# DC-DC-Converters.net
KiCad netlist of a schematic drawn in Altium Designer
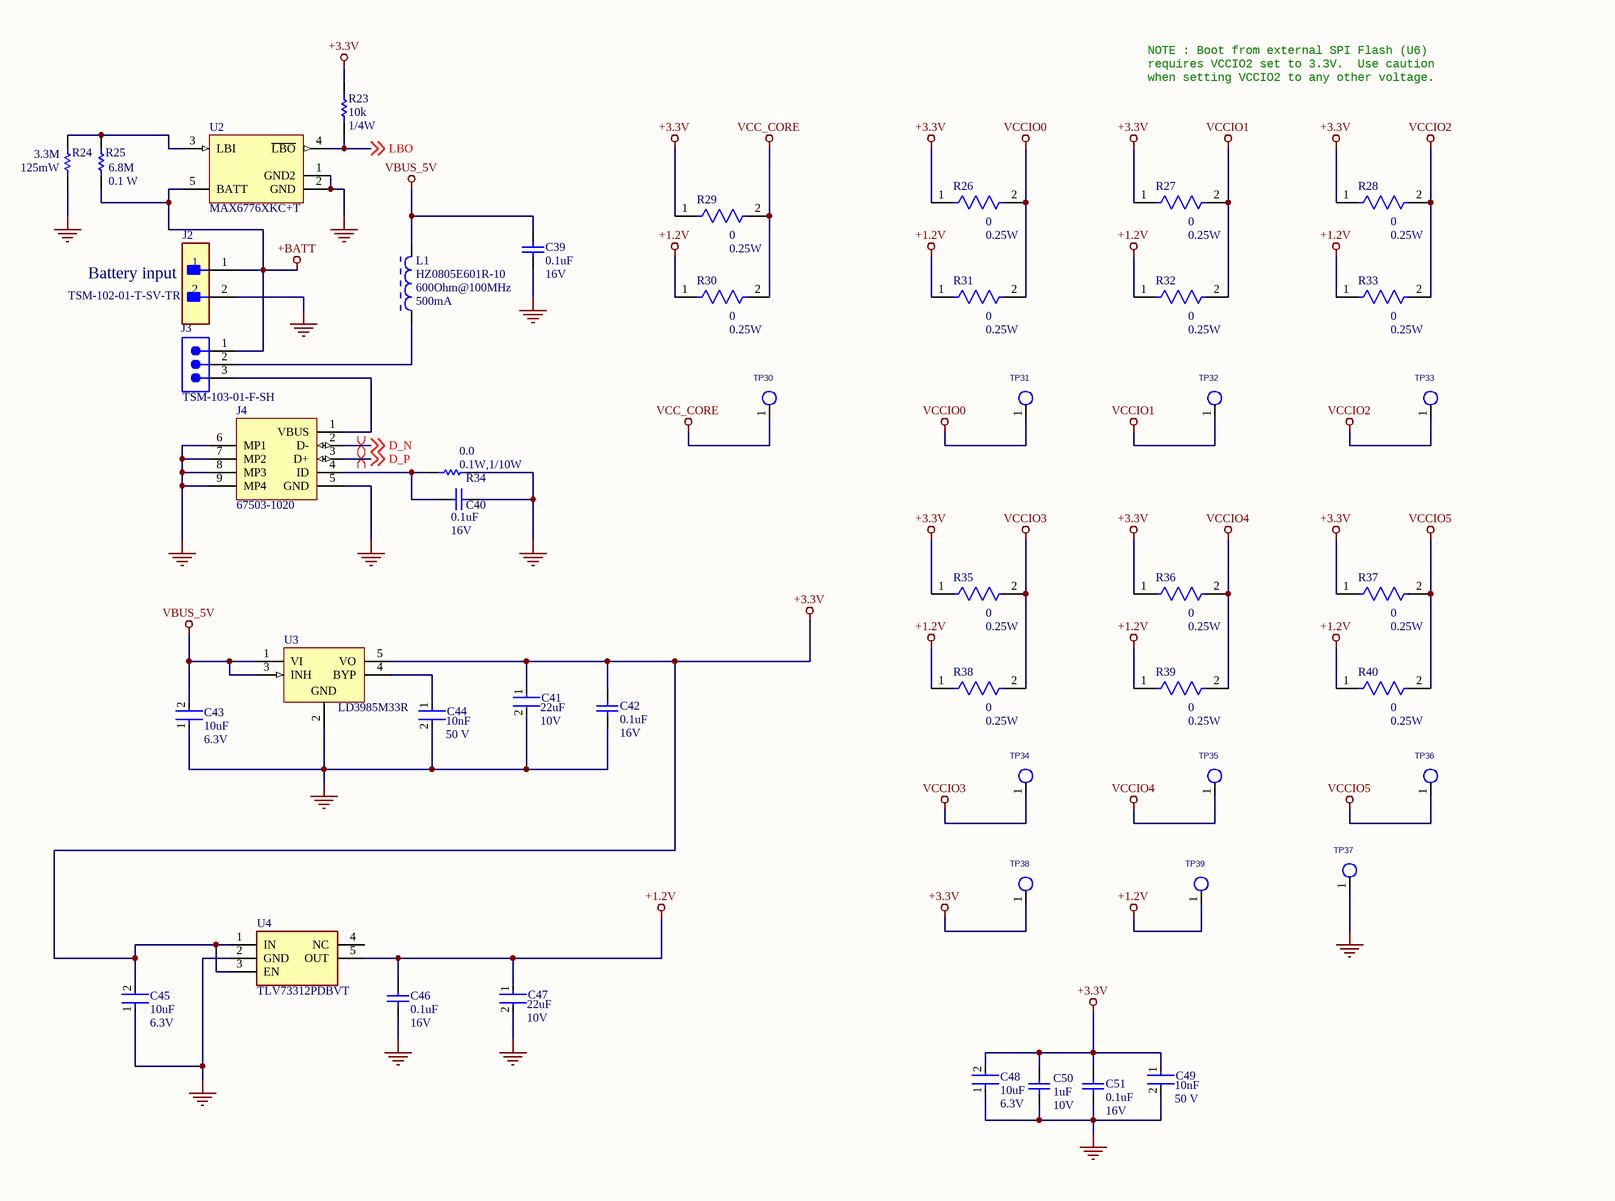
[diagram p0: DC-DC-Converters.SchDoc]

(export (version "E")
  (design (tool "Eeschema 10.0.6"))
  (components
    (comp (ref "C39")
      (value "0.1uF")
      (footprint "CAPC1608X87X35ML15T15")
      (description "Ceramic Capacitor 0.1uF 16V +-10% X7R0603")
      (fields
        (field (name "PART NUMBER") "C0603C104M4RACTU")
        (field (name "MANUFACTURER") "Kemet")
        (field (name "VOLTAGE") "16V")
      )
      (libsource (lib "Altium Content Vault") (part "CAP"))
    )
    (comp (ref "C40")
      (value "0.1uF")
      (footprint "CAPC1608X87X35ML15T15")
      (description "Ceramic Capacitor 0.1uF 16V +-10% X7R0603")
      (fields
        (field (name "PART NUMBER") "C0603C104M4RACTU")
        (field (name "MANUFACTURER") "Kemet")
        (field (name "VOLTAGE") "16V")
      )
      (libsource (lib "Altium Content Vault") (part "CAP"))
    )
    (comp (ref "C41")
      (value "22uF")
      (footprint "FP-GRM188-0_2-IPC_C")
      (description "Chip Multilayer Ceramic Capacitors for General Purpose, 0603, 22uF, X5R, 15%, 20%, 10V")
      (fields
        (field (name "TOLERANCE") "20%")
        (field (name "VOLTAGE") "10V")
        (field (name "PART NUMBER") "GRM188R61A226ME15D")
      )
      (libsource (lib "Altium Content Vault") (part "11868f565c42a9108669ba33697ecf6"))
    )
    (comp (ref "C42")
      (value "0.1uF")
      (footprint "CAPC1608X87X35ML15T15")
      (description "Ceramic Capacitor 0.1uF 16V +-10% X7R0603")
      (fields
        (field (name "PART NUMBER") "C0603C104M4RACTU")
        (field (name "MANUFACTURER") "Kemet")
        (field (name "VOLTAGE") "16V")
      )
      (libsource (lib "Altium Content Vault") (part "CAP"))
    )
    (comp (ref "C43")
      (value "10uF")
      (footprint "FP-CL10-IPC_C")
      (description "Cap Ceramic 10uF 6.3V X5R ±20% Pad SMD 0603 +85°C T/R")
      (fields
        (field (name "VOLTAGE") "6.3V")
        (field (name "TOLERANCE") "20%")
        (field (name "MANUFACTURER") "Samsung")
      )
      (libsource (lib "Altium Content Vault") (part "b4654b650e69147ec39a6b967a45e02"))
    )
    (comp (ref "C44")
      (value "10nF")
      (footprint "FP-C0805C-DN-MFG")
      (description "CAP CER 10000PF 50V X7R 0805")
      (fields
        (field (name "VOLTAGE") "50 V")
        (field (name "PART NUMBER") "C0805C103K5RACAUTO")
        (field (name "MANUFACTURER") "KEMET")
      )
      (libsource (lib "Altium Content Vault") (part "b4654b650e69147ec39a6b967a45e02"))
    )
    (comp (ref "C45")
      (value "10uF")
      (footprint "FP-CL10-IPC_C")
      (description "Cap Ceramic 10uF 6.3V X5R ±20% Pad SMD 0603 +85°C T/R")
      (fields
        (field (name "VOLTAGE") "6.3V")
        (field (name "TOLERANCE") "20%")
        (field (name "MANUFACTURER") "Samsung")
      )
      (libsource (lib "Altium Content Vault") (part "b4654b650e69147ec39a6b967a45e02"))
    )
    (comp (ref "C46")
      (value "0.1uF")
      (footprint "CAPC1608X87X35ML15T15")
      (description "Ceramic Capacitor 0.1uF 16V +-10% X7R0603")
      (fields
        (field (name "PART NUMBER") "C0603C104M4RACTU")
        (field (name "MANUFACTURER") "Kemet")
        (field (name "VOLTAGE") "16V")
      )
      (libsource (lib "Altium Content Vault") (part "CAP"))
    )
    (comp (ref "C47")
      (value "22uF")
      (footprint "FP-GRM188-0_2-IPC_C")
      (description "Chip Multilayer Ceramic Capacitors for General Purpose, 0603, 22uF, X5R, 15%, 20%, 10V")
      (fields
        (field (name "TOLERANCE") "20%")
        (field (name "VOLTAGE") "10V")
        (field (name "PART NUMBER") "GRM188R61A226ME15D")
      )
      (libsource (lib "Altium Content Vault") (part "11868f565c42a9108669ba33697ecf6"))
    )
    (comp (ref "C48")
      (value "10uF")
      (footprint "FP-CL10-IPC_C")
      (description "Cap Ceramic 10uF 6.3V X5R ±20% Pad SMD 0603 +85°C T/R")
      (fields
        (field (name "VOLTAGE") "6.3V")
        (field (name "TOLERANCE") "20%")
        (field (name "MANUFACTURER") "Samsung")
      )
      (libsource (lib "Altium Content Vault") (part "b4654b650e69147ec39a6b967a45e02"))
    )
    (comp (ref "C49")
      (value "10nF")
      (footprint "FP-C0805C-DN-MFG")
      (description "CAP CER 10000PF 50V X7R 0805")
      (fields
        (field (name "VOLTAGE") "50 V")
        (field (name "PART NUMBER") "C0805C103K5RACAUTO")
        (field (name "MANUFACTURER") "KEMET")
      )
      (libsource (lib "Altium Content Vault") (part "b4654b650e69147ec39a6b967a45e02"))
    )
    (comp (ref "C50")
      (value "1uF")
      (footprint "CAPC1608X90X35ML15T15")
      (fields
        (field (name "MANUFACTURER") "Kemet")
        (field (name "PART NUMBER") "C0603C105K8RACTU")
        (field (name "VOLTAGE") "10V")
      )
      (libsource (lib "Altium Content Vault") (part "CAP"))
    )
    (comp (ref "C51")
      (value "0.1uF")
      (footprint "CAPC1608X87X35ML15T15")
      (description "Ceramic Capacitor 0.1uF 16V +-10% X7R0603")
      (fields
        (field (name "PART NUMBER") "C0603C104M4RACTU")
        (field (name "MANUFACTURER") "Kemet")
        (field (name "VOLTAGE") "16V")
      )
      (libsource (lib "Altium Content Vault") (part "CAP"))
    )
    (comp (ref "J2")
      (value "TSM-102-01-T-SV-TR")
      (footprint "FP-TSM-102-01-T-SV-TR-MFG")
      (description "CONN HEADER SMD 2POS 2.54MM")
      (libsource (lib "Altium Content Vault") (part "3bc925449376181038e59eaffc5286c"))
    )
    (comp (ref "J3")
      (value "TSM-103-01-F-SH")
      (footprint "SMTC-TSM-103-01-X-SH-A")
      (fields (field (name "MANUFACTURER") "Samtec") (field (name "PART NUMBER") "TSM-103-01-F-SH"))
      (libsource (lib "Altium Content Vault") (part "SMTC-TSM-103-01-X-SH-A"))
    )
    (comp (ref "J4")
      (value "67503-1020")
      (footprint "MOLX-67503-1020_V")
      (description "USB, MINI, SMD, RA KME04-USBMU03A01")
      (fields (field (name "MANUFACTURER") "Molex"))
      (libsource (lib "Altium Content Vault") (part "MOLX-67503-1020"))
    )
    (comp (ref "L1")
      (value "HZ0805E601R-10")
      (footprint "LIRD-LI0805H151R-10-2_V")
      (fields
        (field (name "IMPEDANCE @ FREQUENCY") "600Ohm@100MHz")
        (field (name "MANUFACTURER") "Laird")
        (field (name "CURRENT RATING (MAX)") "500mA")
      )
      (libsource (lib "Altium Content Vault") (part "IND-FB-2"))
    )
    (comp (ref "R23")
      (value "10k")
      (footprint "RESC3216X70X50NL05T20")
      (description "Res Thick Film 1206 10k Ohms 5% 1/4W")
      (fields
        (field (name "PART NUMBER") "ERJ-8GEYJ103V")
        (field (name "MANUFACTURER") "Panasonic")
        (field (name "POWER") "1/4W")
      )
      (libsource (lib "Altium Content Vault") (part "RES"))
    )
    (comp (ref "R24")
      (value "3.3M")
      (footprint "RESC2013X50X30LL20T20")
      (fields
        (field (name "MANUFACTURER") "Vishay Dale")
        (field (name "PART NUMBER") "CRCW08053M30FKEA")
        (field (name "POWER") "125mW")
      )
      (libsource (lib "Altium Content Vault") (part "RES"))
    )
    (comp (ref "R25")
      (value "6.8M")
      (footprint "RESC0603(1608)_L")
      (description "6M8 0.1W 5% 0603 (1608 Metric)  SMD")
      (fields
        (field (name "POWER") "0.1 W")
        (field (name "TOLERANCE") "5 %")
        (field (name "PART NUMBER") "ERJ-3GEYJ685V")
      )
      (libsource (lib "Altium Content Vault") (part "RES"))
    )
    (comp (ref "R26")
      (value "0")
      (footprint "FP-RC1206-MFG")
      (description "RES SMD 0 OHM JUMPER 1/4W 1206")
      (fields
        (field (name "PART NUMBER") "RC1206JR-070RL")
        (field (name "MANUFACTURER") "YAGEO")
        (field (name "POWER") "0.25W")
      )
      (libsource (lib "Altium Content Vault") (part "1029c3af85768c4190bb7ad29bc67b5"))
    )
    (comp (ref "R27")
      (value "0")
      (footprint "FP-RC1206-MFG")
      (description "RES SMD 0 OHM JUMPER 1/4W 1206")
      (fields
        (field (name "PART NUMBER") "RC1206JR-070RL")
        (field (name "MANUFACTURER") "YAGEO")
        (field (name "POWER") "0.25W")
      )
      (libsource (lib "Altium Content Vault") (part "1029c3af85768c4190bb7ad29bc67b5"))
    )
    (comp (ref "R28")
      (value "0")
      (footprint "FP-RC1206-MFG")
      (description "RES SMD 0 OHM JUMPER 1/4W 1206")
      (fields
        (field (name "PART NUMBER") "RC1206JR-070RL")
        (field (name "MANUFACTURER") "YAGEO")
        (field (name "POWER") "0.25W")
      )
      (libsource (lib "Altium Content Vault") (part "1029c3af85768c4190bb7ad29bc67b5"))
    )
    (comp (ref "R29")
      (value "0")
      (footprint "FP-RC1206-MFG")
      (description "RES SMD 0 OHM JUMPER 1/4W 1206")
      (fields
        (field (name "PART NUMBER") "RC1206JR-070RL")
        (field (name "MANUFACTURER") "YAGEO")
        (field (name "POWER") "0.25W")
      )
      (libsource (lib "Altium Content Vault") (part "1029c3af85768c4190bb7ad29bc67b5"))
    )
    (comp (ref "R30")
      (value "0")
      (footprint "FP-RC1206-MFG")
      (description "RES SMD 0 OHM JUMPER 1/4W 1206")
      (fields
        (field (name "PART NUMBER") "RC1206JR-070RL")
        (field (name "MANUFACTURER") "YAGEO")
        (field (name "POWER") "0.25W")
      )
      (libsource (lib "Altium Content Vault") (part "1029c3af85768c4190bb7ad29bc67b5"))
    )
    (comp (ref "R31")
      (value "0")
      (footprint "FP-RC1206-MFG")
      (description "RES SMD 0 OHM JUMPER 1/4W 1206")
      (fields
        (field (name "PART NUMBER") "RC1206JR-070RL")
        (field (name "MANUFACTURER") "YAGEO")
        (field (name "POWER") "0.25W")
      )
      (libsource (lib "Altium Content Vault") (part "1029c3af85768c4190bb7ad29bc67b5"))
    )
    (comp (ref "R32")
      (value "0")
      (footprint "FP-RC1206-MFG")
      (description "RES SMD 0 OHM JUMPER 1/4W 1206")
      (fields
        (field (name "PART NUMBER") "RC1206JR-070RL")
        (field (name "MANUFACTURER") "YAGEO")
        (field (name "POWER") "0.25W")
      )
      (libsource (lib "Altium Content Vault") (part "1029c3af85768c4190bb7ad29bc67b5"))
    )
    (comp (ref "R33")
      (value "0")
      (footprint "FP-RC1206-MFG")
      (description "RES SMD 0 OHM JUMPER 1/4W 1206")
      (fields
        (field (name "PART NUMBER") "RC1206JR-070RL")
        (field (name "MANUFACTURER") "YAGEO")
        (field (name "POWER") "0.25W")
      )
      (libsource (lib "Altium Content Vault") (part "1029c3af85768c4190bb7ad29bc67b5"))
    )
    (comp (ref "R34")
      (value "0.0")
      (footprint "RESC1608X55X35LL10T10")
      (description "Chip Resistor, 0 Ohm, +/- 5%, 0.1 W, -55 to 155 degC, 0603 (1608 Metric), RoHS, Tape and Reel")
      (fields
        (field (name "POWER") "0.1W,1/10W")
        (field (name "MANUFACTURER") "Samsung-Electro-Mechanics-America,-Inc.")
        (field (name "TOLERANCE") "Jumper")
      )
      (libsource (lib "Altium Content Vault") (part "RES-2"))
    )
    (comp (ref "R35")
      (value "0")
      (footprint "FP-RC1206-MFG")
      (description "RES SMD 0 OHM JUMPER 1/4W 1206")
      (fields
        (field (name "PART NUMBER") "RC1206JR-070RL")
        (field (name "MANUFACTURER") "YAGEO")
        (field (name "POWER") "0.25W")
      )
      (libsource (lib "Altium Content Vault") (part "1029c3af85768c4190bb7ad29bc67b5"))
    )
    (comp (ref "R36")
      (value "0")
      (footprint "FP-RC1206-MFG")
      (description "RES SMD 0 OHM JUMPER 1/4W 1206")
      (fields
        (field (name "PART NUMBER") "RC1206JR-070RL")
        (field (name "MANUFACTURER") "YAGEO")
        (field (name "POWER") "0.25W")
      )
      (libsource (lib "Altium Content Vault") (part "1029c3af85768c4190bb7ad29bc67b5"))
    )
    (comp (ref "R37")
      (value "0")
      (footprint "FP-RC1206-MFG")
      (description "RES SMD 0 OHM JUMPER 1/4W 1206")
      (fields
        (field (name "PART NUMBER") "RC1206JR-070RL")
        (field (name "MANUFACTURER") "YAGEO")
        (field (name "POWER") "0.25W")
      )
      (libsource (lib "Altium Content Vault") (part "1029c3af85768c4190bb7ad29bc67b5"))
    )
    (comp (ref "R38")
      (value "0")
      (footprint "FP-RC1206-MFG")
      (description "RES SMD 0 OHM JUMPER 1/4W 1206")
      (fields
        (field (name "PART NUMBER") "RC1206JR-070RL")
        (field (name "MANUFACTURER") "YAGEO")
        (field (name "POWER") "0.25W")
      )
      (libsource (lib "Altium Content Vault") (part "1029c3af85768c4190bb7ad29bc67b5"))
    )
    (comp (ref "R39")
      (value "0")
      (footprint "FP-RC1206-MFG")
      (description "RES SMD 0 OHM JUMPER 1/4W 1206")
      (fields
        (field (name "PART NUMBER") "RC1206JR-070RL")
        (field (name "MANUFACTURER") "YAGEO")
        (field (name "POWER") "0.25W")
      )
      (libsource (lib "Altium Content Vault") (part "1029c3af85768c4190bb7ad29bc67b5"))
    )
    (comp (ref "R40")
      (value "0")
      (footprint "FP-RC1206-MFG")
      (description "RES SMD 0 OHM JUMPER 1/4W 1206")
      (fields
        (field (name "PART NUMBER") "RC1206JR-070RL")
        (field (name "MANUFACTURER") "YAGEO")
        (field (name "POWER") "0.25W")
      )
      (libsource (lib "Altium Content Vault") (part "1029c3af85768c4190bb7ad29bc67b5"))
    )
    (comp (ref "TP30")
      (value "tp_s_40_63")
      (footprint "tp_s_40_63")
      (description "Square test point, 40mil inner diameter, 63mil outer diameter")
      (libsource (lib "*") (part "TP_S_40_63"))
    )
    (comp (ref "TP31")
      (value "tp_s_40_63")
      (footprint "tp_s_40_63")
      (description "Square test point, 40mil inner diameter, 63mil outer diameter")
      (libsource (lib "*") (part "TP_S_40_63"))
    )
    (comp (ref "TP32")
      (value "tp_s_40_63")
      (footprint "tp_s_40_63")
      (description "Square test point, 40mil inner diameter, 63mil outer diameter")
      (libsource (lib "*") (part "TP_S_40_63"))
    )
    (comp (ref "TP33")
      (value "tp_s_40_63")
      (footprint "tp_s_40_63")
      (description "Square test point, 40mil inner diameter, 63mil outer diameter")
      (libsource (lib "*") (part "TP_S_40_63"))
    )
    (comp (ref "TP34")
      (value "tp_s_40_63")
      (footprint "tp_s_40_63")
      (description "Square test point, 40mil inner diameter, 63mil outer diameter")
      (libsource (lib "*") (part "TP_S_40_63"))
    )
    (comp (ref "TP35")
      (value "tp_s_40_63")
      (footprint "tp_s_40_63")
      (description "Square test point, 40mil inner diameter, 63mil outer diameter")
      (libsource (lib "*") (part "TP_S_40_63"))
    )
    (comp (ref "TP36")
      (value "tp_s_40_63")
      (footprint "tp_s_40_63")
      (description "Square test point, 40mil inner diameter, 63mil outer diameter")
      (libsource (lib "*") (part "TP_S_40_63"))
    )
    (comp (ref "TP37")
      (value "tp_s_40_63")
      (footprint "tp_s_40_63")
      (description "Square test point, 40mil inner diameter, 63mil outer diameter")
      (libsource (lib "*") (part "TP_S_40_63"))
    )
    (comp (ref "TP38")
      (value "tp_s_40_63")
      (footprint "tp_s_40_63")
      (description "Square test point, 40mil inner diameter, 63mil outer diameter")
      (libsource (lib "*") (part "TP_S_40_63"))
    )
    (comp (ref "TP39")
      (value "tp_s_40_63")
      (footprint "tp_s_40_63")
      (description "Square test point, 40mil inner diameter, 63mil outer diameter")
      (libsource (lib "*") (part "TP_S_40_63"))
    )
    (comp (ref "U2")
      (value "MAX6776XKC+T")
      (footprint "X5+1_N")
      (libsource (lib "Altium Content Vault") (part "MAX-MAX6776-SOT5"))
    )
    (comp (ref "U3")
      (value "LD3985M33R")
      (footprint "SOT23-5L_N")
      (libsource (lib "Altium Content Vault") (part "PM-REG-LD3985-SOT5"))
    )
    (comp (ref "U4")
      (value "TLV73312PDBVT")
      (footprint "SamacSys:SOT95P280X145-5N")
      (description "Integrated Circuit")
      (fields (field (name "MOUSER PART NUMBER") "595-TLV73312PDBVT"))
      (libsource (lib "*") (part "TLV73312PDBVT"))
    )
  )
  (nets
    (net (code "1") (name "+1.2V") (class "Default")
      (node (ref "C46") (pin "1") (pinfunction "1_1") (pintype "passive"))
      (node (ref "C47") (pin "1") (pinfunction "1_1") (pintype "passive"))
      (node (ref "R30") (pin "1") (pinfunction "1_1") (pintype "passive"))
      (node (ref "R31") (pin "1") (pinfunction "1_1") (pintype "passive"))
      (node (ref "R32") (pin "1") (pinfunction "1_1") (pintype "passive"))
      (node (ref "R33") (pin "1") (pinfunction "1_1") (pintype "passive"))
      (node (ref "R38") (pin "1") (pinfunction "1_1") (pintype "passive"))
      (node (ref "R39") (pin "1") (pinfunction "1_1") (pintype "passive"))
      (node (ref "R40") (pin "1") (pinfunction "1_1") (pintype "passive"))
      (node (ref "TP39") (pin "1") (pinfunction "TP_1") (pintype "passive"))
      (node (ref "U4") (pin "5") (pinfunction "OUT_5") (pintype "passive"))
    )
    (net (code "2") (name "+3.3V") (class "Default")
      (node (ref "C41") (pin "1") (pinfunction "1_1") (pintype "passive"))
      (node (ref "C42") (pin "1") (pinfunction "1_1") (pintype "passive"))
      (node (ref "C45") (pin "2") (pinfunction "2_2") (pintype "passive"))
      (node (ref "C48") (pin "2") (pinfunction "2_2") (pintype "passive"))
      (node (ref "C49") (pin "1") (pinfunction "1_1") (pintype "passive"))
      (node (ref "C50") (pin "2") (pinfunction "2_2") (pintype "passive"))
      (node (ref "C51") (pin "1") (pinfunction "1_1") (pintype "passive"))
      (node (ref "R23") (pin "1") (pinfunction "1_1") (pintype "passive"))
      (node (ref "R26") (pin "1") (pinfunction "1_1") (pintype "passive"))
      (node (ref "R27") (pin "1") (pinfunction "1_1") (pintype "passive"))
      (node (ref "R28") (pin "1") (pinfunction "1_1") (pintype "passive"))
      (node (ref "R29") (pin "1") (pinfunction "1_1") (pintype "passive"))
      (node (ref "R35") (pin "1") (pinfunction "1_1") (pintype "passive"))
      (node (ref "R36") (pin "1") (pinfunction "1_1") (pintype "passive"))
      (node (ref "R37") (pin "1") (pinfunction "1_1") (pintype "passive"))
      (node (ref "TP38") (pin "1") (pinfunction "TP_1") (pintype "passive"))
      (node (ref "U3") (pin "5") (pinfunction "VO_5") (pintype "power_in"))
      (node (ref "U4") (pin "1") (pinfunction "IN_1") (pintype "passive"))
      (node (ref "U4") (pin "3") (pinfunction "EN_3") (pintype "passive"))
    )
    (net (code "3") (name "+BATT") (class "Default")
      (node (ref "J2") (pin "1") (pinfunction "1_1") (pintype "passive"))
      (node (ref "J3") (pin "1") (pinfunction "1_1") (pintype "passive"))
      (node (ref "R25") (pin "1") (pinfunction "1_1") (pintype "passive"))
      (node (ref "U2") (pin "5") (pinfunction "BATT_5") (pintype "power_in"))
    )
    (net (code "4") (name "D_N") (class "Default")
      (node (ref "J4") (pin "2") (pinfunction "D-_2") (pintype "bidirectional"))
    )
    (net (code "5") (name "D_P") (class "Default")
      (node (ref "J4") (pin "3") (pinfunction "D+_3") (pintype "bidirectional"))
    )
    (net (code "6") (name "GND") (class "Default")
      (node (ref "C39") (pin "2") (pinfunction "2_2") (pintype "passive"))
      (node (ref "C40") (pin "1") (pinfunction "1_1") (pintype "passive"))
      (node (ref "C41") (pin "2") (pinfunction "2_2") (pintype "passive"))
      (node (ref "C42") (pin "2") (pinfunction "2_2") (pintype "passive"))
      (node (ref "C43") (pin "1") (pinfunction "1_1") (pintype "passive"))
      (node (ref "C44") (pin "2") (pinfunction "2_2") (pintype "passive"))
      (node (ref "C45") (pin "1") (pinfunction "1_1") (pintype "passive"))
      (node (ref "C46") (pin "2") (pinfunction "2_2") (pintype "passive"))
      (node (ref "C47") (pin "2") (pinfunction "2_2") (pintype "passive"))
      (node (ref "C48") (pin "1") (pinfunction "1_1") (pintype "passive"))
      (node (ref "C49") (pin "2") (pinfunction "2_2") (pintype "passive"))
      (node (ref "C50") (pin "1") (pinfunction "1_1") (pintype "passive"))
      (node (ref "C51") (pin "2") (pinfunction "2_2") (pintype "passive"))
      (node (ref "J2") (pin "2") (pinfunction "2_2") (pintype "passive"))
      (node (ref "J4") (pin "5") (pinfunction "GND_5") (pintype "power_in"))
      (node (ref "J4") (pin "6") (pinfunction "MP1_6") (pintype "passive"))
      (node (ref "J4") (pin "7") (pinfunction "MP2_7") (pintype "passive"))
      (node (ref "J4") (pin "8") (pinfunction "MP3_8") (pintype "passive"))
      (node (ref "J4") (pin "9") (pinfunction "MP4_9") (pintype "passive"))
      (node (ref "R24") (pin "1") (pinfunction "1_1") (pintype "passive"))
      (node (ref "R34") (pin "2") (pinfunction "2_2") (pintype "passive"))
      (node (ref "TP37") (pin "1") (pinfunction "TP_1") (pintype "passive"))
      (node (ref "U2") (pin "1") (pinfunction "GND2_1") (pintype "power_in"))
      (node (ref "U2") (pin "2") (pinfunction "GND_2") (pintype "power_in"))
      (node (ref "U3") (pin "2") (pinfunction "GND_2") (pintype "power_in"))
      (node (ref "U4") (pin "2") (pinfunction "GND_2") (pintype "passive"))
    )
    (net (code "7") (name "LBO") (class "Default")
      (node (ref "R23") (pin "2") (pinfunction "2_2") (pintype "passive"))
      (node (ref "U2") (pin "4") (pinfunction "~{LBO}_4") (pintype "output"))
    )
    (net (code "8") (name "Net-(J3-Pad2)") (class "Default")
      (node (ref "J3") (pin "2") (pinfunction "2_2") (pintype "passive"))
      (node (ref "L1") (pin "1") (pinfunction "1_1") (pintype "passive"))
    )
    (net (code "9") (name "Net-(J4-ID)") (class "Default")
      (node (ref "C40") (pin "2") (pinfunction "2_2") (pintype "passive"))
      (node (ref "J4") (pin "4") (pinfunction "ID_4") (pintype "passive"))
      (node (ref "R34") (pin "1") (pinfunction "1_1") (pintype "passive"))
    )
    (net (code "10") (name "Net-(J4-VBUS)") (class "Default")
      (node (ref "J3") (pin "3") (pinfunction "3_3") (pintype "passive"))
      (node (ref "J4") (pin "1") (pinfunction "VBUS_1") (pintype "power_in"))
    )
    (net (code "11") (name "Net-(U2-LBI)") (class "Default")
      (node (ref "R24") (pin "2") (pinfunction "2_2") (pintype "passive"))
      (node (ref "R25") (pin "2") (pinfunction "2_2") (pintype "passive"))
      (node (ref "U2") (pin "3") (pinfunction "LBI_3") (pintype "input"))
    )
    (net (code "12") (name "Net-(U3-BYP)") (class "Default")
      (node (ref "C44") (pin "1") (pinfunction "1_1") (pintype "passive"))
      (node (ref "U3") (pin "4") (pinfunction "BYP_4") (pintype "passive"))
    )
    (net (code "13") (name "VBUS_5V") (class "Default")
      (node (ref "C39") (pin "1") (pinfunction "1_1") (pintype "passive"))
      (node (ref "C43") (pin "2") (pinfunction "2_2") (pintype "passive"))
      (node (ref "L1") (pin "2") (pinfunction "2_2") (pintype "passive"))
      (node (ref "U3") (pin "1") (pinfunction "VI_1") (pintype "power_in"))
      (node (ref "U3") (pin "3") (pinfunction "INH_3") (pintype "input"))
    )
    (net (code "14") (name "VCCIO0") (class "Default")
      (node (ref "R26") (pin "2") (pinfunction "2_2") (pintype "passive"))
      (node (ref "R31") (pin "2") (pinfunction "2_2") (pintype "passive"))
      (node (ref "TP31") (pin "1") (pinfunction "TP_1") (pintype "passive"))
    )
    (net (code "15") (name "VCCIO1") (class "Default")
      (node (ref "R27") (pin "2") (pinfunction "2_2") (pintype "passive"))
      (node (ref "R32") (pin "2") (pinfunction "2_2") (pintype "passive"))
      (node (ref "TP32") (pin "1") (pinfunction "TP_1") (pintype "passive"))
    )
    (net (code "16") (name "VCCIO2") (class "Default")
      (node (ref "R28") (pin "2") (pinfunction "2_2") (pintype "passive"))
      (node (ref "R33") (pin "2") (pinfunction "2_2") (pintype "passive"))
      (node (ref "TP33") (pin "1") (pinfunction "TP_1") (pintype "passive"))
    )
    (net (code "17") (name "VCCIO3") (class "Default")
      (node (ref "R35") (pin "2") (pinfunction "2_2") (pintype "passive"))
      (node (ref "R38") (pin "2") (pinfunction "2_2") (pintype "passive"))
      (node (ref "TP34") (pin "1") (pinfunction "TP_1") (pintype "passive"))
    )
    (net (code "18") (name "VCCIO4") (class "Default")
      (node (ref "R36") (pin "2") (pinfunction "2_2") (pintype "passive"))
      (node (ref "R39") (pin "2") (pinfunction "2_2") (pintype "passive"))
      (node (ref "TP35") (pin "1") (pinfunction "TP_1") (pintype "passive"))
    )
    (net (code "19") (name "VCCIO5") (class "Default")
      (node (ref "R37") (pin "2") (pinfunction "2_2") (pintype "passive"))
      (node (ref "R40") (pin "2") (pinfunction "2_2") (pintype "passive"))
      (node (ref "TP36") (pin "1") (pinfunction "TP_1") (pintype "passive"))
    )
    (net (code "20") (name "VCC_CORE") (class "Default")
      (node (ref "R29") (pin "2") (pinfunction "2_2") (pintype "passive"))
      (node (ref "R30") (pin "2") (pinfunction "2_2") (pintype "passive"))
      (node (ref "TP30") (pin "1") (pinfunction "TP_1") (pintype "passive"))
    )
    (net (code "21") (name "unconnected-(U4-NC-Pad4)") (class "Default")
      (node (ref "U4") (pin "4") (pinfunction "NC_4") (pintype "passive"))
    )
  )
)
